# SAMV71_Xplained_Ultra_MCU_Peripherals.net
KiCad netlist of a schematic drawn in Altium Designer
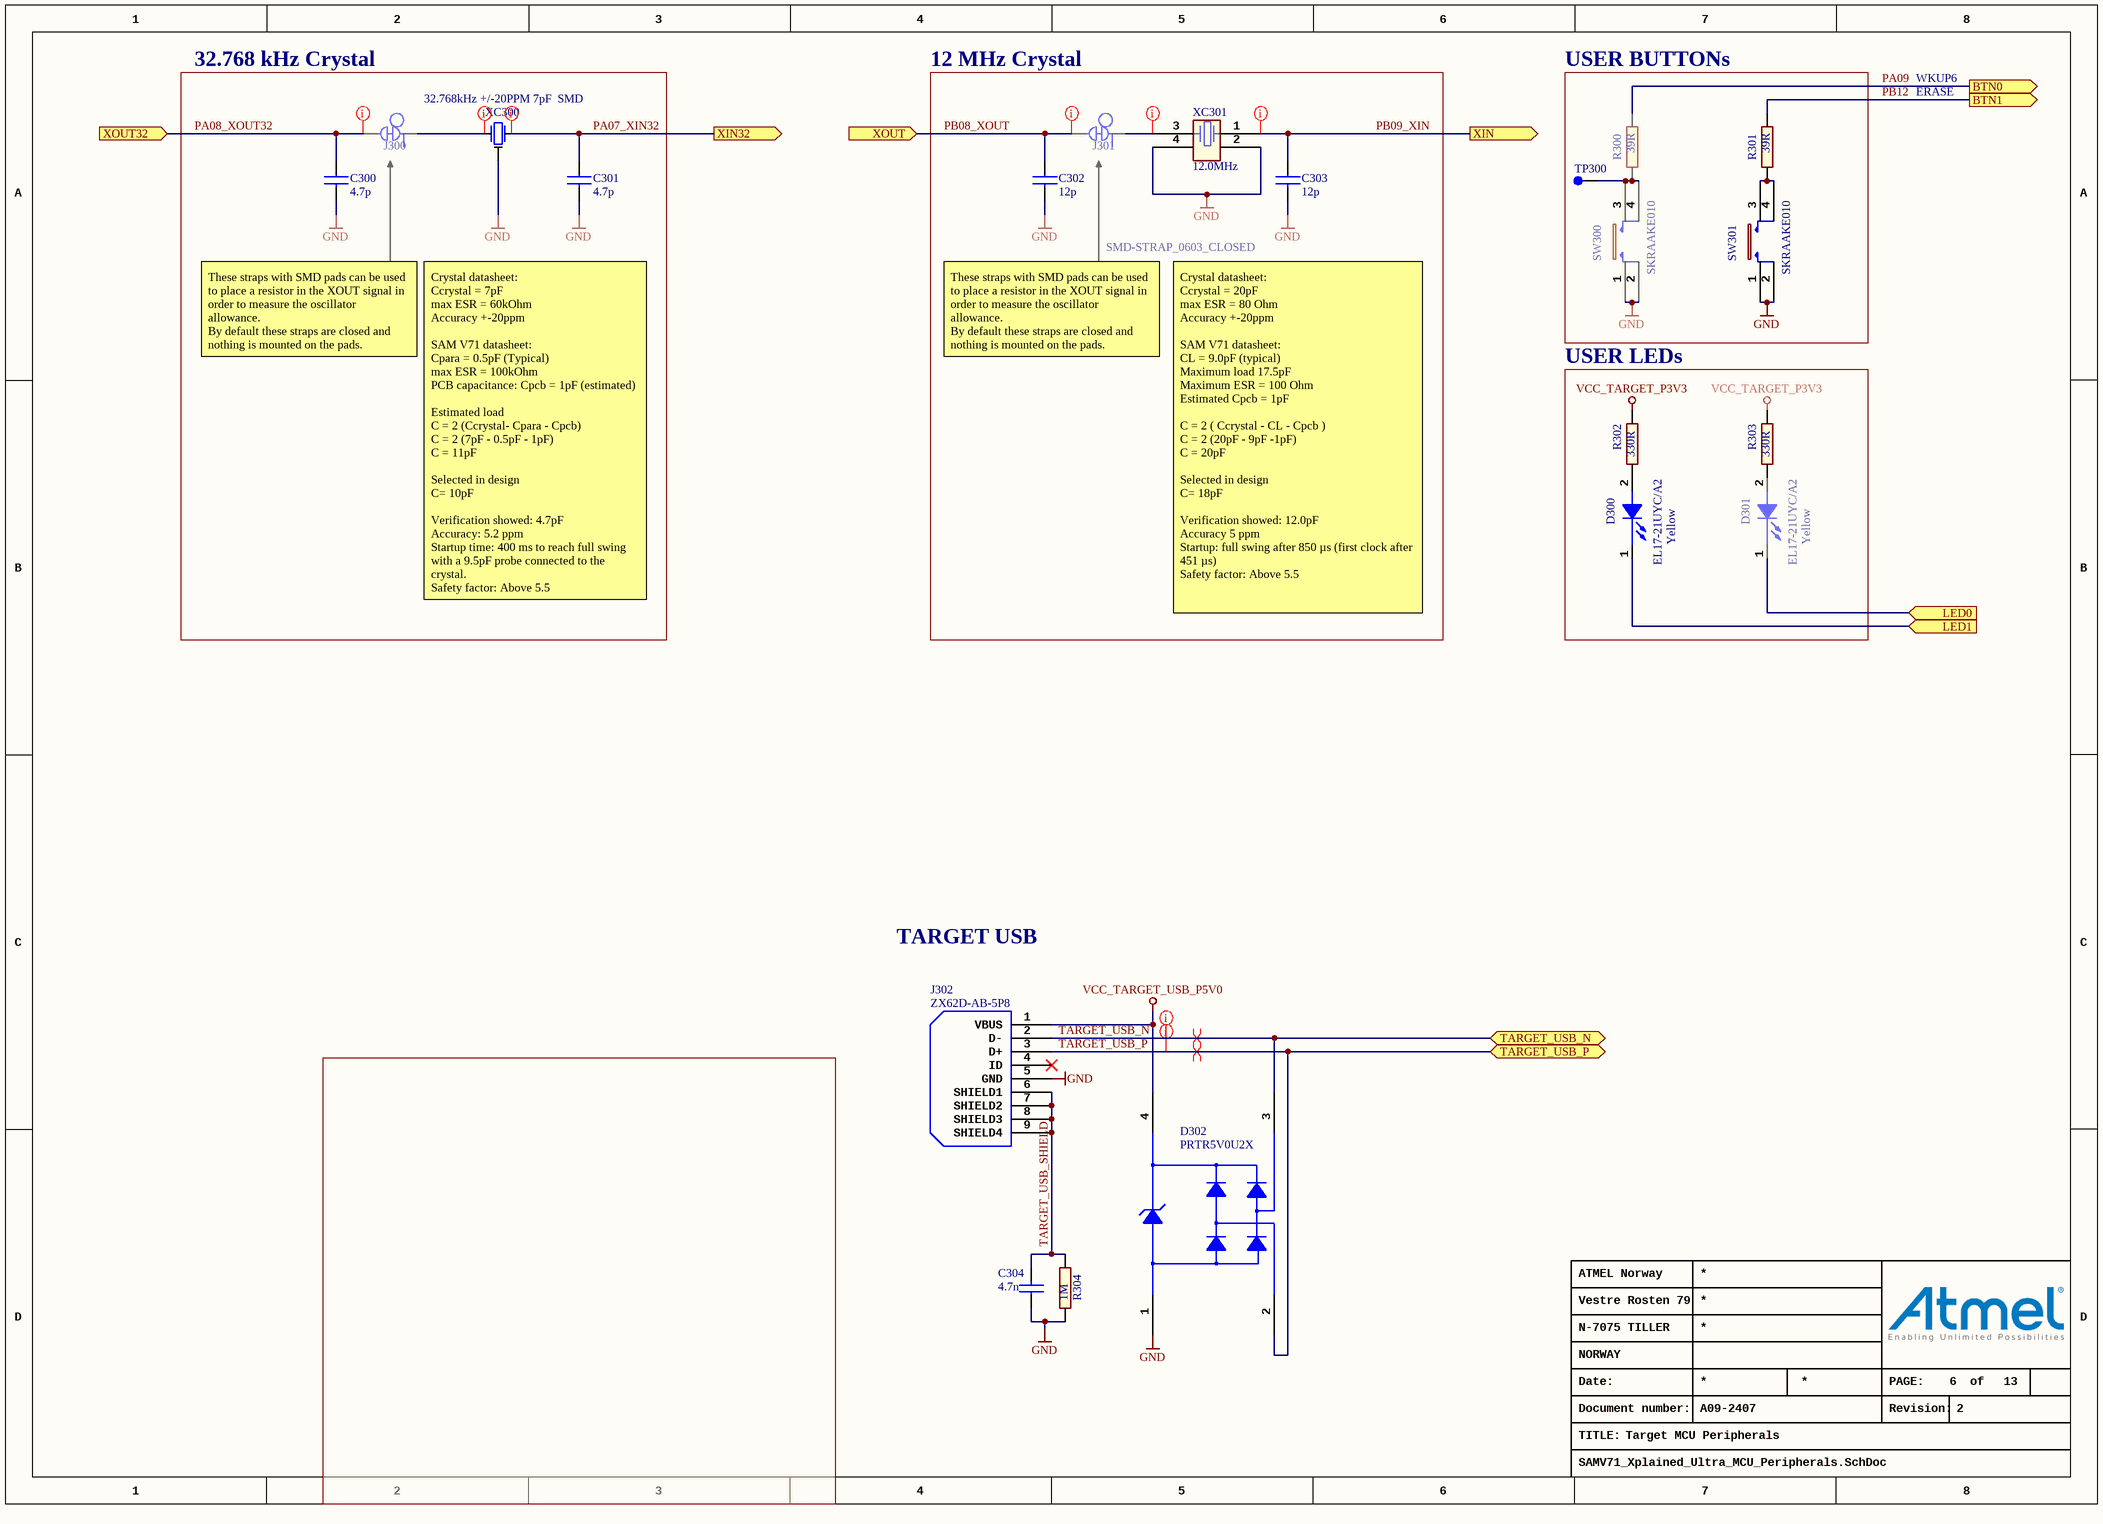
[diagram p0: SAMV71_Xplained_Ultra_MCU_Peripherals.SchDoc]

(export (version "E")
  (design (tool "Eeschema 10.0.6"))
  (components
    (comp (ref "C300")
      (value "4.7p")
      (footprint "AP1-00001")
      (description "Ceramic capacitor, SMD 0402, NP0, 50V, +/-0.25pF")
      (fields (field (name "TOLERANCE") "50V, +/-0.25pF") (field (name "Comment") "CAP-NONPOL"))
      (libsource (lib "AltiumDbLib") (part "CAP-NONPOL"))
    )
    (comp (ref "C301")
      (value "4.7p")
      (footprint "AP1-00001")
      (description "Ceramic capacitor, SMD 0402, NP0, 50V, +/-0.25pF")
      (fields (field (name "TOLERANCE") "50V, +/-0.25pF") (field (name "Comment") "CAP-NONPOL"))
      (libsource (lib "AltiumDbLib") (part "CAP-NONPOL"))
    )
    (comp (ref "C302")
      (value "12p")
      (footprint "AP1-00001")
      (description "Ceramic capacitor, SMD 0402, NP0, 50V, +/-5%")
      (fields (field (name "TOLERANCE") "50V, +/-5%") (field (name "Comment") "CAP-NONPOL"))
      (libsource (lib "AltiumDbLib") (part "CAP-NONPOL"))
    )
    (comp (ref "C303")
      (value "12p")
      (footprint "AP1-00001")
      (description "Ceramic capacitor, SMD 0402, NP0, 50V, +/-5%")
      (fields (field (name "TOLERANCE") "50V, +/-5%") (field (name "Comment") "CAP-NONPOL"))
      (libsource (lib "AltiumDbLib") (part "CAP-NONPOL"))
    )
    (comp (ref "C304")
      (value "4.7n")
      (footprint "AP1-00053")
      (description "Ceramic capacitor, SMD 0402, X7R, 25V, +/-10%")
      (fields (field (name "TOLERANCE") "25V, +/-10%") (field (name "Comment") "CAP-NONPOL"))
      (libsource (lib "AltiumDbLib") (part "CAP-NONPOL"))
    )
    (comp (ref "D300")
      (value "Yellow")
      (footprint "AP4-00013")
      (description "LED, Yellow, Wave length=591nm, SMD 0805, ±70°")
      (fields
        (field (name "ALTIUM_VALUE") "EL17-21UYC/A2")
        (field (name "MANUFACTURER") "Everlight")
        (field (name "MPN") "17-21UYC/S530-A3/TR8")
      )
      (libsource (lib "AltiumDbLib") (part "LED_12"))
    )
    (comp (ref "D301")
      (value "Yellow")
      (footprint "AP4-00013")
      (description "LED, Yellow, Wave length=591nm, SMD 0805, ±70°")
      (fields
        (field (name "ALTIUM_VALUE") "EL17-21UYC/A2")
        (field (name "MANUFACTURER") "Everlight")
        (field (name "MPN") "17-21UYC/S530-A3/TR8")
      )
      (libsource (lib "AltiumDbLib") (part "LED_12"))
    )
    (comp (ref "D302")
      (value "PRTR5V0U2X")
      (footprint "AP4-00001")
      (description "Double rail-to-rail USB ESD protection diode")
      (fields (field (name "MANUFACTURER") "Philips"))
      (libsource (lib "AltiumDbLib") (part "PRTR5V0U2X"))
    )
    (comp (ref "J300")
      (value "~")
      (footprint "AP9-00044")
      (description "Default closed SMD strap, 0603 size")
      (libsource (lib "AltiumDbLib") (part "SMD-STRAP_CLOSED"))
    )
    (comp (ref "J301")
      (value "SMD-STRAP_0603_CLOSED")
      (footprint "AP9-00044")
      (description "Default closed SMD strap, 0603 size")
      (libsource (lib "AltiumDbLib") (part "SMD-STRAP_CLOSED"))
    )
    (comp (ref "J302")
      (value "ZX62D-AB-5P8")
      (footprint "AP8-00852")
      (description "Micro USB AB Connector, Standard SMT + DIP")
      (fields (field (name "Comment") "2,000 pieces per reel"))
      (libsource (lib "AltiumDbLib") (part "USB_AB"))
    )
    (comp (ref "R300")
      (value "39R")
      (footprint "AP2-00011")
      (description "Thick film resistor, SMD 0402, 1/16W, 1%")
      (fields (field (name "TOLERANCE") "1 %") (field (name "Comment") "R2"))
      (libsource (lib "AltiumDbLib") (part "R2"))
    )
    (comp (ref "R301")
      (value "39R")
      (footprint "AP2-00011")
      (description "Thick film resistor, SMD 0402, 1/16W, 1%")
      (fields (field (name "TOLERANCE") "1 %") (field (name "Comment") "R2"))
      (libsource (lib "AltiumDbLib") (part "R2"))
    )
    (comp (ref "R302")
      (value "330R")
      (footprint "AP2-00000")
      (description "Thick film resistor, SMD 0402, 1/16W, 1%")
      (fields (field (name "TOLERANCE") "1 %") (field (name "Comment") "R2"))
      (libsource (lib "") (part "R2_1"))
    )
    (comp (ref "R303")
      (value "330R")
      (footprint "AP2-00000")
      (description "Thick film resistor, SMD 0402, 1/16W, 1%")
      (fields (field (name "TOLERANCE") "1 %") (field (name "Comment") "R2"))
      (libsource (lib "") (part "R2_1"))
    )
    (comp (ref "R304")
      (value "1M")
      (footprint "AP2-00011")
      (description "Thick film resistor, SMD 0402, 1/16W, 1%")
      (fields (field (name "TOLERANCE") "1 %") (field (name "MANUFACTURER") "KOA"))
      (libsource (lib "AltiumDbLib") (part "R2"))
    )
    (comp (ref "SW300")
      (value "SKRAAKE010")
      (footprint "AP8-00137")
      (description "6.2x6.2 mm SMD tact switch, same as A08-0091 but less force is needed")
      (fields
        (field (name "MANUFACTURER") "ALPS")
        (field (name "Comment") "Can be ordered in low volumes from Mouser")
      )
      (libsource (lib "AltiumDbLib") (part "PUSHBUTTON1"))
    )
    (comp (ref "SW301")
      (value "SKRAAKE010")
      (footprint "AP8-00137")
      (description "6.2x6.2 mm SMD tact switch, same as A08-0091 but less force is needed")
      (fields
        (field (name "MANUFACTURER") "ALPS")
        (field (name "Comment") "Can be ordered in low volumes from Mouser")
      )
      (libsource (lib "AltiumDbLib") (part "PUSHBUTTON1"))
    )
    (comp (ref "TP300")
      (value "TESTPOINT")
      (footprint "AP8-00010")
      (description "Single SMD testpad")
      (libsource (lib "AltiumDbLib") (part "TESTPOINT"))
    )
    (comp (ref "XC300")
      (value "32.768kHz +/-20PPM 7pF  SMD")
      (footprint "AP7-00044")
      (description "32k768 crystal, +-20ppm, CL=7pF, max ESR 60kOhm, SMD")
      (fields (field (name "TOLERANCE") "+/- 20 PPM") (field (name "MANUFACTURER") "Micro Crystal"))
      (libsource (lib "AltiumDbLib") (part "CRYSTAL_2P_metal"))
    )
    (comp (ref "XC301")
      (value "12.0MHz")
      (footprint "AP7-00039")
      (description "Fox FQ5032B 12.0MHz SMD crystal 738B-12")
      (fields (field (name "TOLERANCE") "30PPM") (field (name "MANUFACTURER") "Fox  Electronics"))
      (libsource (lib "AltiumDbLib") (part "CRYSTAL1324"))
    )
  )
  (nets
    (net (code "1") (name "/LED0") (class "Default")
      (node (ref "D301") (pin "1") (pinfunction "CATHODE_1") (pintype "passive"))
    )
    (net (code "2") (name "/LED1") (class "Default")
      (node (ref "D300") (pin "1") (pinfunction "CATHODE_1") (pintype "passive"))
    )
    (net (code "3") (name "/PA07_XIN32") (class "Default")
      (node (ref "C301") (pin "1") (pinfunction "1_1") (pintype "passive"))
      (node (ref "XC300") (pin "2") (pinfunction "2_2") (pintype "passive"))
    )
    (net (code "4") (name "/PA08_XOUT32") (class "Default")
      (node (ref "C300") (pin "1") (pinfunction "1_1") (pintype "passive"))
      (node (ref "J300") (pin "2") (pinfunction "2_2") (pintype "passive"))
    )
    (net (code "5") (name "/PA09") (class "Default")
      (node (ref "R300") (pin "2") (pinfunction "2_2") (pintype "passive"))
    )
    (net (code "6") (name "/PB08_XOUT") (class "Default")
      (node (ref "C302") (pin "1") (pinfunction "1_1") (pintype "passive"))
      (node (ref "J301") (pin "2") (pinfunction "2_2") (pintype "passive"))
    )
    (net (code "7") (name "/PB09_XIN") (class "Default")
      (node (ref "C303") (pin "1") (pinfunction "1_1") (pintype "passive"))
      (node (ref "XC301") (pin "1") (pinfunction "1_1") (pintype "passive"))
    )
    (net (code "8") (name "/PB12") (class "Default")
      (node (ref "R301") (pin "2") (pinfunction "2_2") (pintype "passive"))
    )
    (net (code "9") (name "/TARGET_USB_N") (class "Default")
      (node (ref "D302") (pin "3") (pinfunction "I/O_2_3") (pintype "passive"))
      (node (ref "J302") (pin "2") (pinfunction "D-_2") (pintype "passive"))
    )
    (net (code "10") (name "/TARGET_USB_P") (class "Default")
      (node (ref "D302") (pin "2") (pinfunction "I/O_1_2") (pintype "passive"))
      (node (ref "J302") (pin "3") (pinfunction "D+_3") (pintype "passive"))
    )
    (net (code "11") (name "/TARGET_USB_SHIELD") (class "Default")
      (node (ref "C304") (pin "2") (pinfunction "2_2") (pintype "passive"))
      (node (ref "J302") (pin "6") (pinfunction "SHIELD1_6") (pintype "passive"))
      (node (ref "J302") (pin "7") (pinfunction "SHIELD2_7") (pintype "passive"))
      (node (ref "J302") (pin "8") (pinfunction "SHIELD3_8") (pintype "passive"))
      (node (ref "J302") (pin "9") (pinfunction "SHIELD4_9") (pintype "passive"))
      (node (ref "R304") (pin "2") (pinfunction "2_2") (pintype "passive"))
    )
    (net (code "12") (name "GND") (class "Default")
      (node (ref "C300") (pin "2") (pinfunction "2_2") (pintype "passive"))
      (node (ref "C301") (pin "2") (pinfunction "2_2") (pintype "passive"))
      (node (ref "C302") (pin "2") (pinfunction "2_2") (pintype "passive"))
      (node (ref "C303") (pin "2") (pinfunction "2_2") (pintype "passive"))
      (node (ref "C304") (pin "1") (pinfunction "1_1") (pintype "passive"))
      (node (ref "D302") (pin "1") (pinfunction "GND_1") (pintype "passive"))
      (node (ref "J302") (pin "5") (pinfunction "GND_5") (pintype "passive"))
      (node (ref "R304") (pin "1") (pinfunction "1_1") (pintype "passive"))
      (node (ref "SW300") (pin "1") (pinfunction "1_1") (pintype "passive"))
      (node (ref "SW300") (pin "2") (pinfunction "2_2") (pintype "passive"))
      (node (ref "SW301") (pin "1") (pinfunction "1_1") (pintype "passive"))
      (node (ref "SW301") (pin "2") (pinfunction "2_2") (pintype "passive"))
      (node (ref "XC300") (pin "3") (pinfunction "3_3") (pintype "passive"))
      (node (ref "XC301") (pin "2") (pinfunction "2_2") (pintype "passive"))
      (node (ref "XC301") (pin "4") (pinfunction "4_4") (pintype "passive"))
    )
    (net (code "13") (name "Net-(D300-ANODE)") (class "Default")
      (node (ref "D300") (pin "2") (pinfunction "ANODE_2") (pintype "passive"))
      (node (ref "R302") (pin "1") (pinfunction "1_1") (pintype "passive"))
    )
    (net (code "14") (name "Net-(D301-ANODE)") (class "Default")
      (node (ref "D301") (pin "2") (pinfunction "ANODE_2") (pintype "passive"))
      (node (ref "R303") (pin "1") (pinfunction "1_1") (pintype "passive"))
    )
    (net (code "15") (name "Net-(J300-Pad1)") (class "Default")
      (node (ref "J300") (pin "1") (pinfunction "1_1") (pintype "passive"))
      (node (ref "XC300") (pin "1") (pinfunction "1_1") (pintype "passive"))
    )
    (net (code "16") (name "Net-(J301-Pad1)") (class "Default")
      (node (ref "J301") (pin "1") (pinfunction "1_1") (pintype "passive"))
      (node (ref "XC301") (pin "3") (pinfunction "3_3") (pintype "passive"))
    )
    (net (code "17") (name "Net-(R300-Pad1)") (class "Default")
      (node (ref "R300") (pin "1") (pinfunction "1_1") (pintype "passive"))
      (node (ref "SW300") (pin "3") (pinfunction "3_3") (pintype "passive"))
      (node (ref "SW300") (pin "4") (pinfunction "4_4") (pintype "passive"))
      (node (ref "TP300") (pin "1") (pinfunction "1_1") (pintype "passive"))
    )
    (net (code "18") (name "Net-(R301-Pad1)") (class "Default")
      (node (ref "R301") (pin "1") (pinfunction "1_1") (pintype "passive"))
      (node (ref "SW301") (pin "3") (pinfunction "3_3") (pintype "passive"))
      (node (ref "SW301") (pin "4") (pinfunction "4_4") (pintype "passive"))
    )
    (net (code "19") (name "VCC_TARGET_P3V3") (class "Default")
      (node (ref "R302") (pin "2") (pinfunction "2_2") (pintype "passive"))
      (node (ref "R303") (pin "2") (pinfunction "2_2") (pintype "passive"))
    )
    (net (code "20") (name "VCC_TARGET_USB_P5V0") (class "Default")
      (node (ref "D302") (pin "4") (pinfunction "VCC_4") (pintype "passive"))
      (node (ref "J302") (pin "1") (pinfunction "VBUS_1") (pintype "passive"))
    )
    (net (code "21") (name "unconnected-(J302-ID-Pad4)") (class "Default")
      (node (ref "J302") (pin "4") (pinfunction "ID_4") (pintype "passive+no_connect"))
    )
  )
)
